# 397881-L.net
KiCad netlist of a schematic drawn in Altium Designer
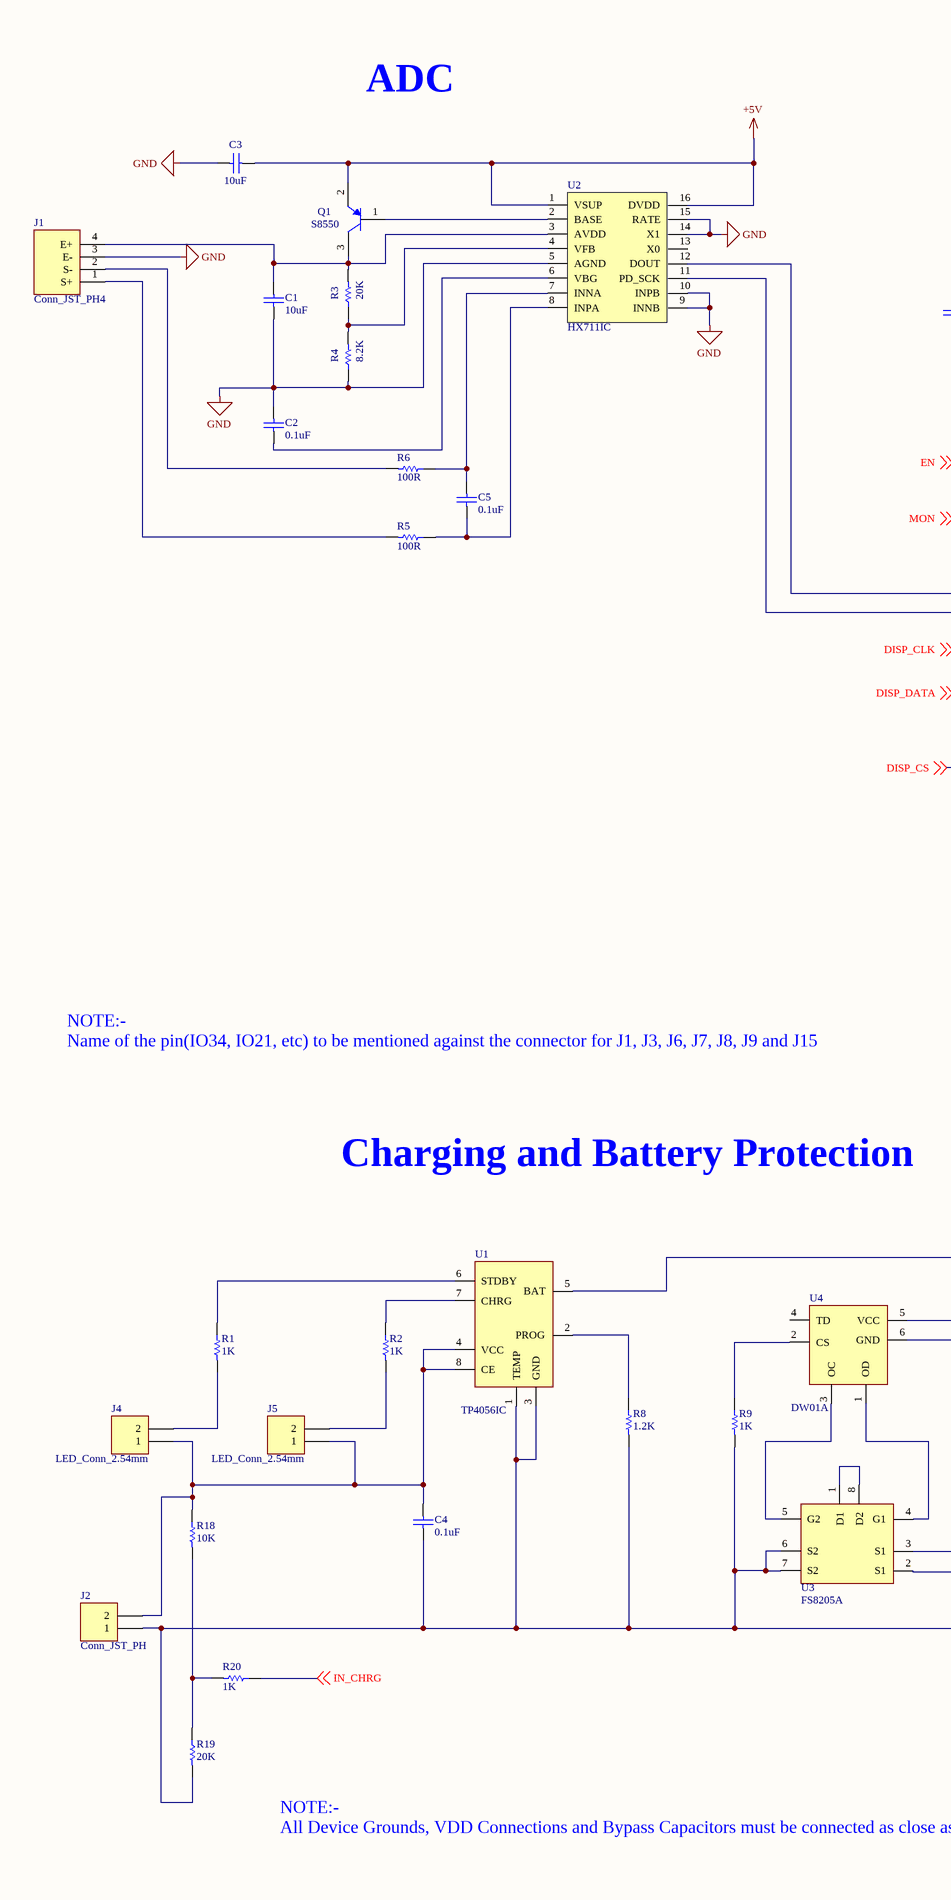
[diagram p0: 397881-L.SchDoc, left]
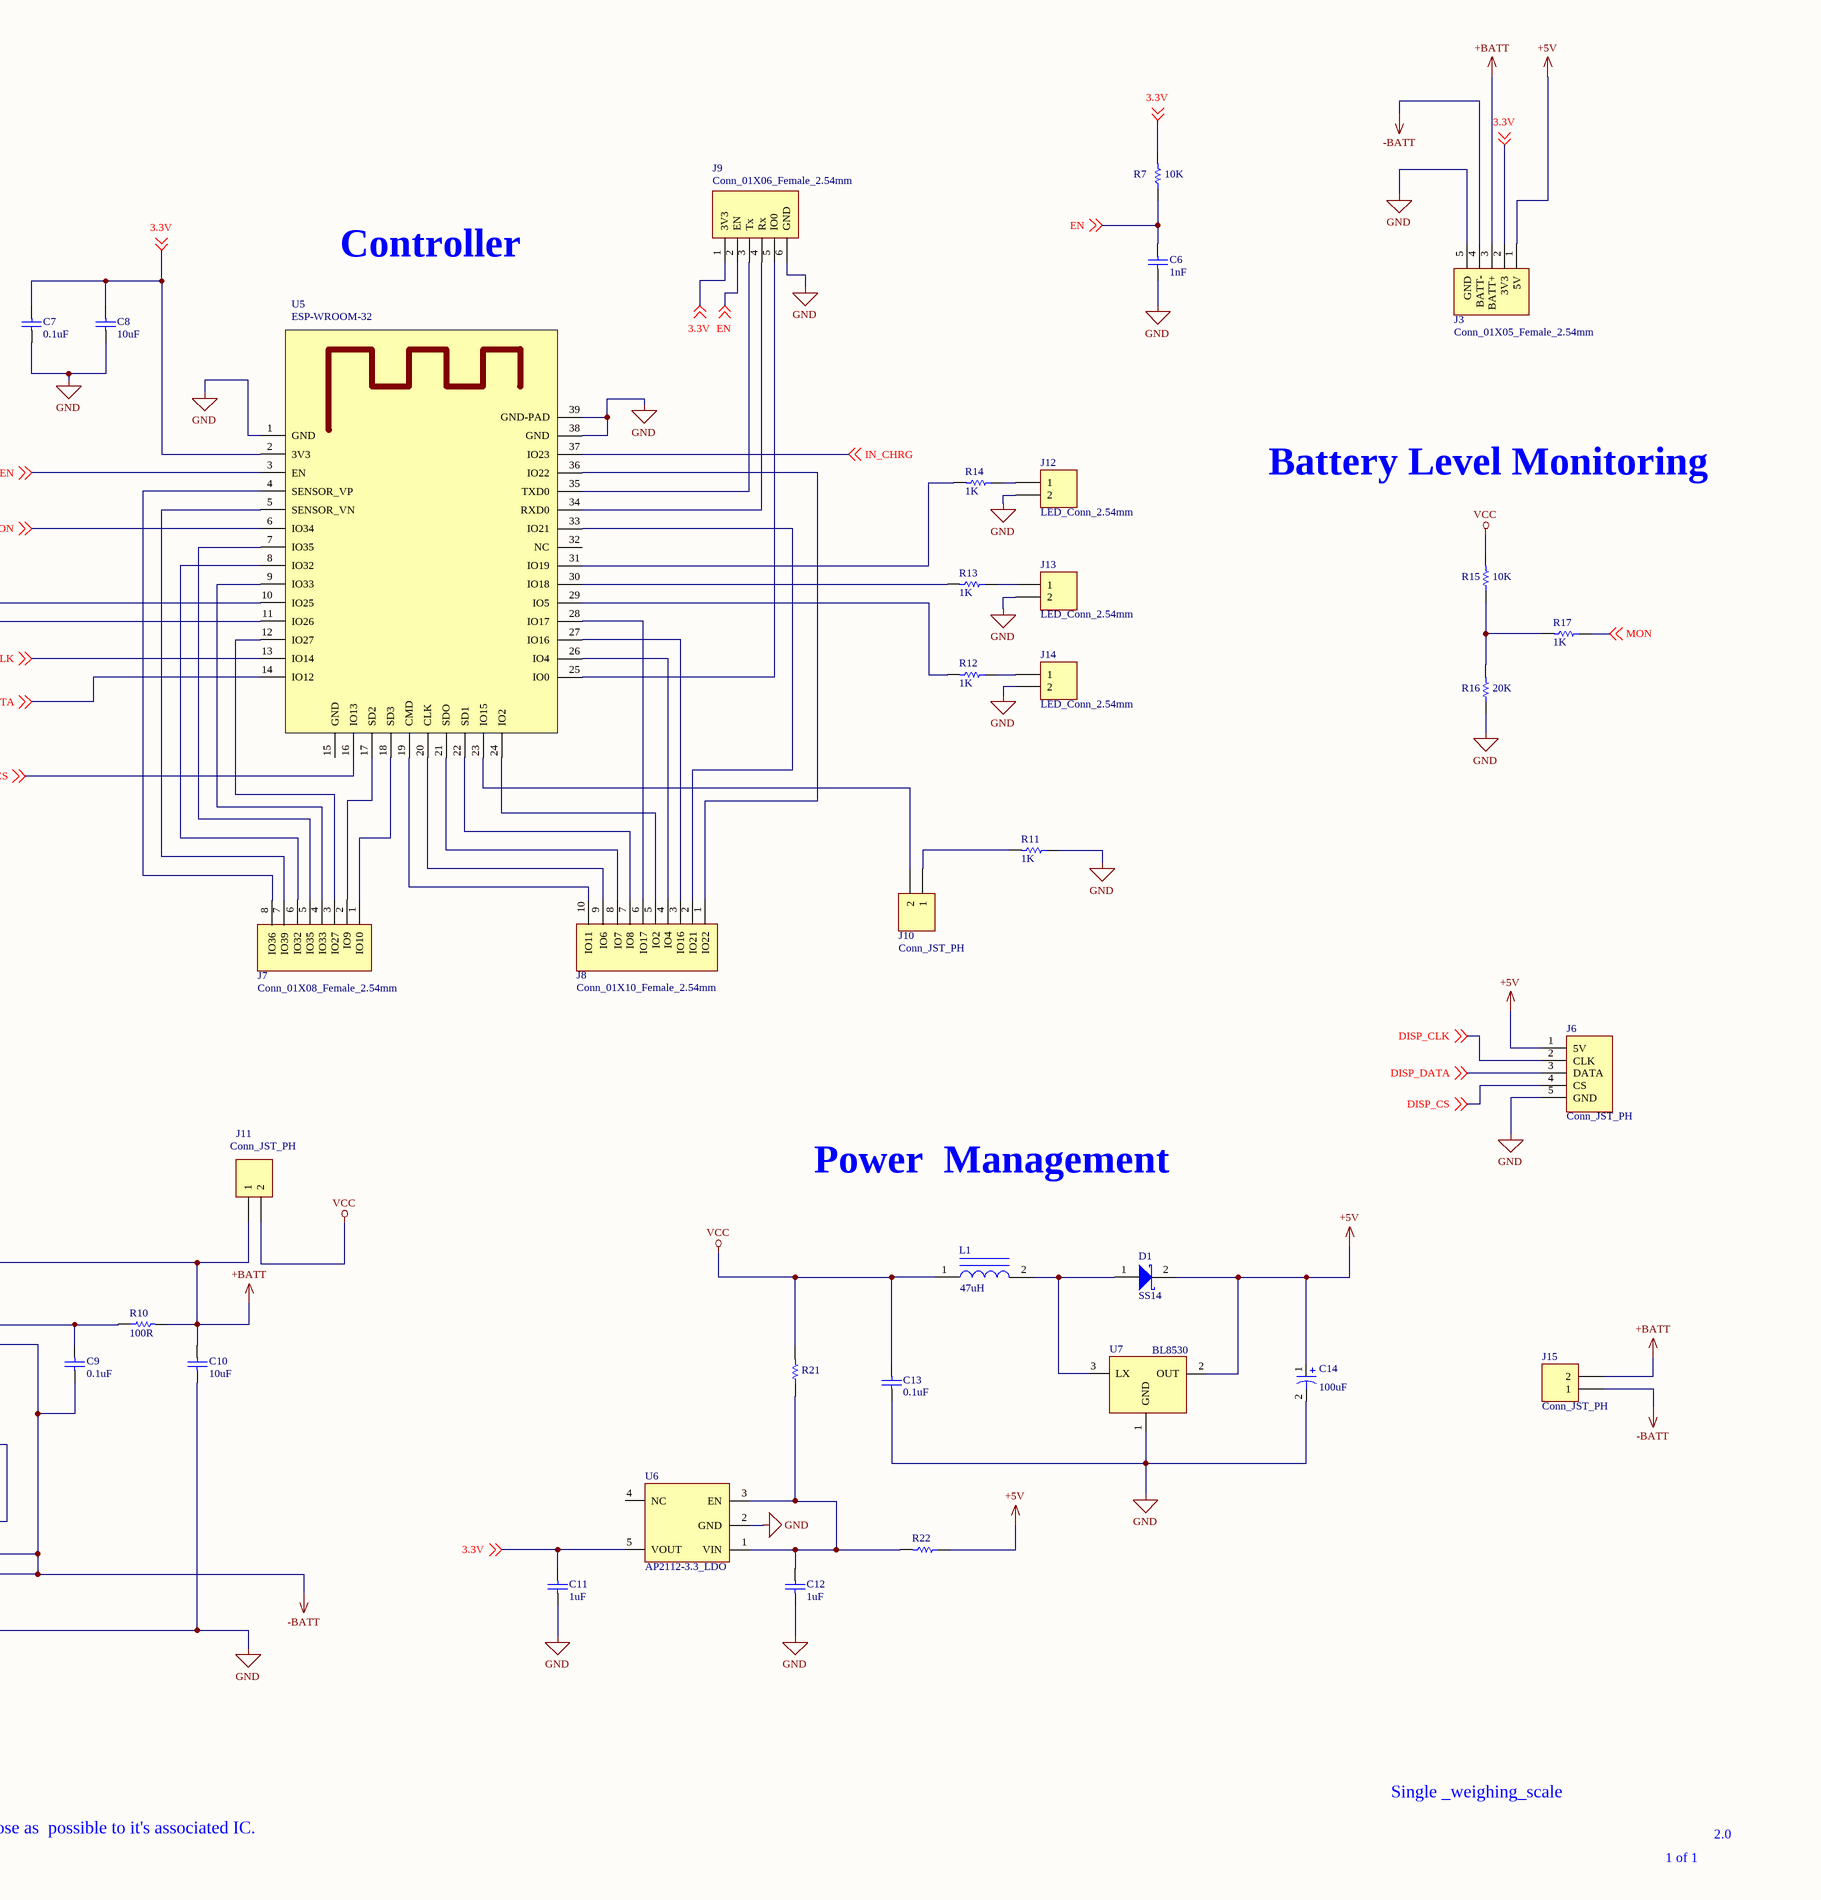
[diagram p1: 397881-L.SchDoc, right]

(export (version "E")
  (design (tool "Eeschema 10.0.6"))
  (components
    (comp (ref "C1")
      (value "10uF")
      (footprint "C0603")
      (description "Capacitor")
      (fields (field (name "Comment") "Cap") (field (name "PUBLISHER") "Altium Limited"))
      (libsource (lib "Miscellaneous Devices") (part "Cap"))
    )
    (comp (ref "C2")
      (value "0.1uF")
      (footprint "C0603")
      (description "Capacitor")
      (fields (field (name "Comment") "Cap") (field (name "PUBLISHER") "Altium Limited"))
      (libsource (lib "Miscellaneous Devices") (part "Cap"))
    )
    (comp (ref "C3")
      (value "10uF")
      (footprint "C0603")
      (description "Capacitor")
      (fields (field (name "Comment") "Cap") (field (name "PUBLISHER") "Altium Limited"))
      (libsource (lib "Miscellaneous Devices") (part "Cap"))
    )
    (comp (ref "C4")
      (value "0.1uF")
      (footprint "C0603")
      (description "Capacitor")
      (fields (field (name "Comment") "Cap") (field (name "PUBLISHER") "Altium Limited"))
      (libsource (lib "Miscellaneous Devices") (part "Cap"))
    )
    (comp (ref "C5")
      (value "0.1uF")
      (footprint "C0603")
      (description "Capacitor")
      (fields (field (name "Comment") "Cap") (field (name "PUBLISHER") "Altium Limited"))
      (libsource (lib "Miscellaneous Devices") (part "Cap"))
    )
    (comp (ref "C6")
      (value "1nF")
      (footprint "C0603")
      (description "Capacitor")
      (fields (field (name "Comment") "Cap") (field (name "PUBLISHER") "Altium Limited"))
      (libsource (lib "Miscellaneous Devices") (part "Cap"))
    )
    (comp (ref "C7")
      (value "0.1uF")
      (footprint "C0603")
      (description "Capacitor")
      (fields (field (name "Comment") "Cap") (field (name "PUBLISHER") "Altium Limited"))
      (libsource (lib "Miscellaneous Devices") (part "Cap"))
    )
    (comp (ref "C8")
      (value "10uF")
      (footprint "C0603")
      (description "Capacitor")
      (fields (field (name "Comment") "Cap") (field (name "PUBLISHER") "Altium Limited"))
      (libsource (lib "Miscellaneous Devices") (part "Cap"))
    )
    (comp (ref "C9")
      (value "0.1uF")
      (footprint "C0603")
      (description "Capacitor")
      (fields (field (name "Comment") "Cap") (field (name "PUBLISHER") "Altium Limited"))
      (libsource (lib "Miscellaneous Devices") (part "Cap"))
    )
    (comp (ref "C10")
      (value "10uF")
      (footprint "C0603")
      (description "Capacitor")
      (fields (field (name "Comment") "Cap") (field (name "PUBLISHER") "Altium Limited"))
      (libsource (lib "Miscellaneous Devices") (part "Cap"))
    )
    (comp (ref "C11")
      (value "1uF")
      (footprint "C0603")
      (description "Capacitor")
      (fields (field (name "Comment") "Cap") (field (name "PUBLISHER") "Altium Limited"))
      (libsource (lib "Miscellaneous Devices") (part "Cap"))
    )
    (comp (ref "C12")
      (value "1uF")
      (footprint "C0603")
      (description "Capacitor")
      (fields (field (name "Comment") "Cap") (field (name "PUBLISHER") "Altium Limited"))
      (libsource (lib "Miscellaneous Devices") (part "Cap"))
    )
    (comp (ref "C13")
      (value "0.1uF")
      (footprint "C0603")
      (description "Capacitor")
      (fields (field (name "Comment") "Cap") (field (name "PUBLISHER") "Altium Limited"))
      (libsource (lib "Miscellaneous Devices") (part "Cap"))
    )
    (comp (ref "C14")
      (value "100uF")
      (footprint "C14")
      (description "Polarized Capacitor (Radial)")
      (fields (field (name "Comment") "Cap Pol1") (field (name "PUBLISHER") "Altium Limited"))
      (libsource (lib "Miscellaneous Devices") (part "Cap Pol1"))
    )
    (comp (ref "D1")
      (value "SS14")
      (footprint "D1")
      (description "Schottky Diode")
      (fields (field (name "PUBLISHER") "Altium Limited"))
      (libsource (lib "Miscellaneous Devices") (part "D Schottky"))
    )
    (comp (ref "J1")
      (value "Conn_JST_PH4")
      (footprint "J1")
      (description "Header, 5-Pin")
      (fields (field (name "PUBLISHER") "Altium Limited"))
      (libsource (lib "397881-L") (part "Conn_JST_PH4"))
    )
    (comp (ref "J2")
      (value "Conn_JST_PH")
      (footprint "J2,J10,J11,J15")
      (description "Header, 2-Pin")
      (fields (field (name "PUBLISHER") "Altium Limited"))
      (libsource (lib "") (part "Header 2_1"))
    )
    (comp (ref "J3")
      (value "Conn_01X05_Female_2.54mm")
      (footprint "J3")
      (description "Header, 6-Pin")
      (fields (field (name "PUBLISHER") "Altium Limited"))
      (libsource (lib "397881-L") (part "Conn_01X05_Female_2.54mm"))
    )
    (comp (ref "J4")
      (value "LED_Conn_2.54mm")
      (footprint "J4,J5,J12,J13,J14")
      (description "Header, 2-Pin")
      (fields (field (name "PUBLISHER") "Altium Limited"))
      (libsource (lib "") (part "Header 2_1"))
    )
    (comp (ref "J5")
      (value "LED_Conn_2.54mm")
      (footprint "J4,J5,J12,J13,J14")
      (description "Header, 2-Pin")
      (fields (field (name "PUBLISHER") "Altium Limited"))
      (libsource (lib "") (part "Header 2_1"))
    )
    (comp (ref "J6")
      (value "Conn_JST_PH")
      (footprint "J6")
      (description "Header, 5-Pin")
      (fields (field (name "PUBLISHER") "Altium Limited"))
      (libsource (lib "397881-L") (part "Conn_JST_PH"))
    )
    (comp (ref "J7")
      (value "Conn_01X08_Female_2.54mm")
      (footprint "J7")
      (description "Header, 6-Pin")
      (fields (field (name "PUBLISHER") "Altium Limited"))
      (libsource (lib "397881-L") (part "Conn_01X08_Female_2.54mm"))
    )
    (comp (ref "J8")
      (value "Conn_01X10_Female_2.54mm")
      (footprint "J8")
      (description "Header, 6-Pin")
      (fields (field (name "PUBLISHER") "Altium Limited"))
      (libsource (lib "397881-L") (part "Conn_01X10_Female_2.54mm"))
    )
    (comp (ref "J9")
      (value "Conn_01X06_Female_2.54mm")
      (footprint "J9")
      (description "Header, 6-Pin")
      (fields (field (name "PUBLISHER") "Altium Limited"))
      (libsource (lib "397881-L") (part "Conn_01X06_Female_2.54mm"))
    )
    (comp (ref "J10")
      (value "Conn_JST_PH")
      (footprint "J2,J10,J11,J15")
      (description "Header, 2-Pin")
      (fields (field (name "PUBLISHER") "Altium Limited"))
      (libsource (lib "") (part "Header 2_2"))
    )
    (comp (ref "J11")
      (value "Conn_JST_PH")
      (footprint "J2,J10,J11,J15")
      (description "Header, 2-Pin")
      (fields (field (name "PUBLISHER") "Altium Limited"))
      (libsource (lib "") (part "Header 2_3"))
    )
    (comp (ref "J12")
      (value "LED_Conn_2.54mm")
      (footprint "J4,J5,J12,J13,J14")
      (description "Header, 2-Pin")
      (fields (field (name "PUBLISHER") "Altium Limited"))
      (libsource (lib "Miscellaneous Connectors") (part "Header 2"))
    )
    (comp (ref "J13")
      (value "LED_Conn_2.54mm")
      (footprint "J4,J5,J12,J13,J14")
      (description "Header, 2-Pin")
      (fields (field (name "PUBLISHER") "Altium Limited"))
      (libsource (lib "Miscellaneous Connectors") (part "Header 2"))
    )
    (comp (ref "J14")
      (value "LED_Conn_2.54mm")
      (footprint "J4,J5,J12,J13,J14")
      (description "Header, 2-Pin")
      (fields (field (name "PUBLISHER") "Altium Limited"))
      (libsource (lib "Miscellaneous Connectors") (part "Header 2"))
    )
    (comp (ref "J15")
      (value "Conn_JST_PH")
      (footprint "J2,J10,J11,J15")
      (description "Header, 2-Pin")
      (fields (field (name "PUBLISHER") "Altium Limited"))
      (libsource (lib "") (part "Header 2_1"))
    )
    (comp (ref "L1")
      (value "47uH")
      (footprint "L1")
      (description "Magnetic-Core Inductor")
      (fields (field (name "Comment") "Inductor Iron") (field (name "PUBLISHER") "Altium Limited"))
      (libsource (lib "Miscellaneous Devices") (part "Inductor Iron"))
    )
    (comp (ref "Q1")
      (value "S8550")
      (footprint "Q1")
      (description "PNP Bipolar Transistor")
      (fields (field (name "PUBLISHER") "Altium Limited"))
      (libsource (lib "Miscellaneous Devices") (part "PNP"))
    )
    (comp (ref "R1")
      (value "1K")
      (footprint "R0603")
      (description "Resistor")
      (fields (field (name "Comment") "Res1") (field (name "PUBLISHER") "Altium Limited"))
      (libsource (lib "Miscellaneous Devices") (part "Res1"))
    )
    (comp (ref "R2")
      (value "1K")
      (footprint "R0603")
      (description "Resistor")
      (fields (field (name "Comment") "Res1") (field (name "PUBLISHER") "Altium Limited"))
      (libsource (lib "Miscellaneous Devices") (part "Res1"))
    )
    (comp (ref "R3")
      (value "20K")
      (footprint "R0603")
      (description "Resistor")
      (fields (field (name "Comment") "Res1") (field (name "PUBLISHER") "Altium Limited"))
      (libsource (lib "Miscellaneous Devices") (part "Res1"))
    )
    (comp (ref "R4")
      (value "8.2K")
      (footprint "R0603")
      (description "Resistor")
      (fields (field (name "Comment") "Res1") (field (name "PUBLISHER") "Altium Limited"))
      (libsource (lib "Miscellaneous Devices") (part "Res1"))
    )
    (comp (ref "R5")
      (value "100R")
      (footprint "R0603")
      (description "Resistor")
      (fields (field (name "Comment") "Res1") (field (name "PUBLISHER") "Altium Limited"))
      (libsource (lib "Miscellaneous Devices") (part "Res1"))
    )
    (comp (ref "R6")
      (value "100R")
      (footprint "R0603")
      (description "Resistor")
      (fields (field (name "Comment") "Res1") (field (name "PUBLISHER") "Altium Limited"))
      (libsource (lib "Miscellaneous Devices") (part "Res1"))
    )
    (comp (ref "R7")
      (value "10K")
      (footprint "R0603")
      (description "Resistor")
      (fields (field (name "Comment") "Res1") (field (name "PUBLISHER") "Altium Limited"))
      (libsource (lib "Miscellaneous Devices") (part "Res1"))
    )
    (comp (ref "R8")
      (value "1.2K")
      (footprint "R0603")
      (description "Resistor")
      (fields (field (name "Comment") "Res1") (field (name "PUBLISHER") "Altium Limited"))
      (libsource (lib "Miscellaneous Devices") (part "Res1"))
    )
    (comp (ref "R9")
      (value "1K")
      (footprint "R0603")
      (description "Resistor")
      (fields (field (name "Comment") "Res1") (field (name "PUBLISHER") "Altium Limited"))
      (libsource (lib "Miscellaneous Devices") (part "Res1"))
    )
    (comp (ref "R10")
      (value "100R")
      (footprint "R0603")
      (description "Resistor")
      (fields (field (name "Comment") "Res1") (field (name "PUBLISHER") "Altium Limited"))
      (libsource (lib "Miscellaneous Devices") (part "Res1"))
    )
    (comp (ref "R11")
      (value "1K")
      (footprint "R0603")
      (description "Resistor")
      (fields (field (name "Comment") "Res1") (field (name "PUBLISHER") "Altium Limited"))
      (libsource (lib "Miscellaneous Devices") (part "Res1"))
    )
    (comp (ref "R12")
      (value "1K")
      (footprint "R0603")
      (description "Resistor")
      (fields (field (name "Comment") "Res1") (field (name "PUBLISHER") "Altium Limited"))
      (libsource (lib "Miscellaneous Devices") (part "Res1"))
    )
    (comp (ref "R13")
      (value "1K")
      (footprint "R0603")
      (description "Resistor")
      (fields (field (name "Comment") "Res1") (field (name "PUBLISHER") "Altium Limited"))
      (libsource (lib "Miscellaneous Devices") (part "Res1"))
    )
    (comp (ref "R14")
      (value "1K")
      (footprint "R0603")
      (description "Resistor")
      (fields (field (name "Comment") "Res1") (field (name "PUBLISHER") "Altium Limited"))
      (libsource (lib "Miscellaneous Devices") (part "Res1"))
    )
    (comp (ref "R15")
      (value "10K")
      (footprint "R0603")
      (description "Resistor")
      (fields (field (name "Comment") "Res1") (field (name "PUBLISHER") "Altium Limited"))
      (libsource (lib "Miscellaneous Devices") (part "Res1"))
    )
    (comp (ref "R16")
      (value "20K")
      (footprint "R0603")
      (description "Resistor")
      (fields (field (name "Comment") "Res1") (field (name "PUBLISHER") "Altium Limited"))
      (libsource (lib "Miscellaneous Devices") (part "Res1"))
    )
    (comp (ref "R17")
      (value "1K")
      (footprint "R0603")
      (description "Resistor")
      (fields (field (name "Comment") "Res1") (field (name "PUBLISHER") "Altium Limited"))
      (libsource (lib "Miscellaneous Devices") (part "Res1"))
    )
    (comp (ref "R18")
      (value "10K")
      (footprint "R0603")
      (description "Resistor")
      (fields (field (name "Comment") "Res1") (field (name "PUBLISHER") "Altium Limited"))
      (libsource (lib "Miscellaneous Devices") (part "Res1"))
    )
    (comp (ref "R19")
      (value "20K")
      (footprint "R0603")
      (description "Resistor")
      (fields (field (name "Comment") "Res1") (field (name "PUBLISHER") "Altium Limited"))
      (libsource (lib "Miscellaneous Devices") (part "Res1"))
    )
    (comp (ref "R20")
      (value "1K")
      (footprint "R0603")
      (description "Resistor")
      (fields (field (name "Comment") "Res1") (field (name "PUBLISHER") "Altium Limited"))
      (libsource (lib "Miscellaneous Devices") (part "Res1"))
    )
    (comp (ref "R21")
      (value "Res1")
      (footprint "R0603")
      (description "Resistor")
      (fields (field (name "PUBLISHER") "Altium Limited"))
      (libsource (lib "Miscellaneous Devices") (part "Res1"))
    )
    (comp (ref "R22")
      (value "Res1")
      (footprint "R0603")
      (description "Resistor")
      (fields (field (name "PUBLISHER") "Altium Limited"))
      (libsource (lib "Miscellaneous Devices") (part "Res1"))
    )
    (comp (ref "U1") (value "TP4056IC") (footprint "U1") (libsource (lib "397881-L") (part "TP4056IC")))
    (comp (ref "U2") (value "HX711IC") (libsource (lib "397881-L") (part "HX711IC")))
    (comp (ref "U3") (value "FS8205A") (footprint "U3") (libsource (lib "397881-L") (part "FS8205A")))
    (comp (ref "U4") (value "DW01A") (footprint "U4") (libsource (lib "397881-L") (part "DW01A")))
    (comp (ref "U5")
      (value "ESP-WROOM-32")
      (footprint "U5")
      (libsource (lib "397881-L") (part "ESP-WROOM-32"))
    )
    (comp (ref "U6")
      (value "AP2112-3.3_LDO")
      (footprint "U6")
      (libsource (lib "397881-L") (part "AP2112-3.3_LDO"))
    )
    (comp (ref "U7") (value "BL8530") (footprint "U7") (libsource (lib "397881-L") (part "BL8530")))
  )
  (nets
    (net (code "1") (name "+5V") (class "Default")
      (node (ref "C14") (pin "1") (pinfunction "1_1") (pintype "passive"))
      (node (ref "C3") (pin "2") (pinfunction "2_2") (pintype "passive"))
      (node (ref "D1") (pin "2") (pinfunction "K_2") (pintype "passive"))
      (node (ref "J3") (pin "1") (pinfunction "5V_1") (pintype "passive"))
      (node (ref "J6") (pin "1") (pinfunction "5V_1") (pintype "passive"))
      (node (ref "Q1") (pin "2") (pinfunction "E_2") (pintype "passive"))
      (node (ref "R22") (pin "1") (pinfunction "1_1") (pintype "passive"))
      (node (ref "U2") (pin "1") (pinfunction "VSUP_1") (pintype "passive"))
      (node (ref "U2") (pin "16") (pinfunction "DVDD_16") (pintype "passive"))
      (node (ref "U7") (pin "2") (pinfunction "OUT_2") (pintype "passive"))
    )
    (net (code "2") (name "+BATT") (class "Default")
      (node (ref "C10") (pin "2") (pinfunction "2_2") (pintype "passive"))
      (node (ref "J11") (pin "1") (pinfunction "1_1") (pintype "passive"))
      (node (ref "J15") (pin "2") (pinfunction "2_2") (pintype "passive"))
      (node (ref "J3") (pin "3") (pinfunction "BATT+_3") (pintype "passive"))
      (node (ref "R10") (pin "2") (pinfunction "2_2") (pintype "passive"))
      (node (ref "U1") (pin "5") (pinfunction "BAT_5") (pintype "passive"))
    )
    (net (code "3") (name "-BATT") (class "Default")
      (node (ref "C9") (pin "1") (pinfunction "1_1") (pintype "passive"))
      (node (ref "J15") (pin "1") (pinfunction "1_1") (pintype "passive"))
      (node (ref "J3") (pin "4") (pinfunction "BATT-_4") (pintype "passive"))
      (node (ref "U3") (pin "2") (pinfunction "S1_2") (pintype "passive"))
      (node (ref "U3") (pin "3") (pinfunction "S1_3") (pintype "passive"))
      (node (ref "U4") (pin "6") (pinfunction "GND_6") (pintype "passive"))
    )
    (net (code "4") (name "3.3V") (class "Default")
      (node (ref "C11") (pin "2") (pinfunction "2_2") (pintype "passive"))
      (node (ref "C7") (pin "2") (pinfunction "2_2") (pintype "passive"))
      (node (ref "C8") (pin "2") (pinfunction "2_2") (pintype "passive"))
      (node (ref "J3") (pin "2") (pinfunction "3V3_2") (pintype "passive"))
      (node (ref "J9") (pin "1") (pinfunction "3V3_1") (pintype "passive"))
      (node (ref "R7") (pin "2") (pinfunction "2_2") (pintype "passive"))
      (node (ref "U5") (pin "2") (pinfunction "3V3_2") (pintype "passive"))
      (node (ref "U6") (pin "5") (pinfunction "VOUT_5") (pintype "passive"))
    )
    (net (code "5") (name "DISP_CLK") (class "Default")
      (node (ref "J6") (pin "2") (pinfunction "CLK_2") (pintype "passive"))
      (node (ref "U5") (pin "13") (pinfunction "IO14_13") (pintype "passive"))
    )
    (net (code "6") (name "DISP_CS") (class "Default")
      (node (ref "J6") (pin "4") (pinfunction "CS_4") (pintype "passive"))
      (node (ref "U5") (pin "16") (pinfunction "IO13_16") (pintype "passive"))
    )
    (net (code "7") (name "DISP_DATA") (class "Default")
      (node (ref "J6") (pin "3") (pinfunction "DATA_3") (pintype "passive"))
      (node (ref "U5") (pin "14") (pinfunction "IO12_14") (pintype "passive"))
    )
    (net (code "8") (name "EN") (class "Default")
      (node (ref "C6") (pin "2") (pinfunction "2_2") (pintype "passive"))
      (node (ref "J9") (pin "2") (pinfunction "EN_2") (pintype "passive"))
      (node (ref "R7") (pin "1") (pinfunction "1_1") (pintype "passive"))
      (node (ref "U5") (pin "3") (pinfunction "EN_3") (pintype "passive"))
    )
    (net (code "9") (name "GND") (class "Default")
      (node (ref "C1") (pin "1") (pinfunction "1_1") (pintype "passive"))
      (node (ref "C10") (pin "1") (pinfunction "1_1") (pintype "passive"))
      (node (ref "C11") (pin "1") (pinfunction "1_1") (pintype "passive"))
      (node (ref "C12") (pin "1") (pinfunction "1_1") (pintype "passive"))
      (node (ref "C13") (pin "1") (pinfunction "1_1") (pintype "passive"))
      (node (ref "C14") (pin "2") (pinfunction "2_2") (pintype "passive"))
      (node (ref "C2") (pin "2") (pinfunction "2_2") (pintype "passive"))
      (node (ref "C3") (pin "1") (pinfunction "1_1") (pintype "passive"))
      (node (ref "C4") (pin "1") (pinfunction "1_1") (pintype "passive"))
      (node (ref "C6") (pin "1") (pinfunction "1_1") (pintype "passive"))
      (node (ref "C7") (pin "1") (pinfunction "1_1") (pintype "passive"))
      (node (ref "C8") (pin "1") (pinfunction "1_1") (pintype "passive"))
      (node (ref "J1") (pin "3") (pinfunction "E-_3") (pintype "passive"))
      (node (ref "J12") (pin "2") (pinfunction "2_2") (pintype "passive"))
      (node (ref "J13") (pin "2") (pinfunction "2_2") (pintype "passive"))
      (node (ref "J14") (pin "2") (pinfunction "2_2") (pintype "passive"))
      (node (ref "J2") (pin "1") (pinfunction "1_1") (pintype "passive"))
      (node (ref "J3") (pin "5") (pinfunction "GND_5") (pintype "passive"))
      (node (ref "J6") (pin "5") (pinfunction "GND_5") (pintype "passive"))
      (node (ref "J9") (pin "6") (pinfunction "GND_6") (pintype "passive"))
      (node (ref "R11") (pin "1") (pinfunction "1_1") (pintype "passive"))
      (node (ref "R16") (pin "1") (pinfunction "1_1") (pintype "passive"))
      (node (ref "R19") (pin "2") (pinfunction "2_2") (pintype "passive"))
      (node (ref "R4") (pin "1") (pinfunction "1_1") (pintype "passive"))
      (node (ref "R8") (pin "2") (pinfunction "2_2") (pintype "passive"))
      (node (ref "R9") (pin "2") (pinfunction "2_2") (pintype "passive"))
      (node (ref "U1") (pin "1") (pinfunction "TEMP_1") (pintype "passive"))
      (node (ref "U1") (pin "3") (pinfunction "GND_3") (pintype "passive"))
      (node (ref "U2") (pin "10") (pinfunction "INPB_10") (pintype "passive"))
      (node (ref "U2") (pin "14") (pinfunction "X1_14") (pintype "passive"))
      (node (ref "U2") (pin "15") (pinfunction "RATE_15") (pintype "passive"))
      (node (ref "U2") (pin "5") (pinfunction "AGND_5") (pintype "passive"))
      (node (ref "U2") (pin "9") (pinfunction "INNB_9") (pintype "passive"))
      (node (ref "U3") (pin "6") (pinfunction "S2_6") (pintype "passive"))
      (node (ref "U3") (pin "7") (pinfunction "S2_7") (pintype "passive"))
      (node (ref "U5") (pin "1") (pinfunction "GND_1") (pintype "passive"))
      (node (ref "U5") (pin "38") (pinfunction "GND_38") (pintype "passive"))
      (node (ref "U5") (pin "39") (pinfunction "GND-PAD_39") (pintype "passive"))
      (node (ref "U6") (pin "2") (pinfunction "GND_2") (pintype "passive"))
      (node (ref "U7") (pin "1") (pinfunction "GND_1") (pintype "passive"))
    )
    (net (code "10") (name "IN_CHRG") (class "Default")
      (node (ref "R20") (pin "1") (pinfunction "1_1") (pintype "passive"))
      (node (ref "U5") (pin "37") (pinfunction "IO23_37") (pintype "passive"))
    )
    (net (code "11") (name "MON") (class "Default")
      (node (ref "R17") (pin "1") (pinfunction "1_1") (pintype "passive"))
      (node (ref "U5") (pin "6") (pinfunction "IO34_6") (pintype "passive"))
    )
    (net (code "12") (name "Net-(D1-A)") (class "Default")
      (node (ref "D1") (pin "1") (pinfunction "A_1") (pintype "passive"))
      (node (ref "L1") (pin "2") (pinfunction "2_2") (pintype "passive"))
      (node (ref "U7") (pin "3") (pinfunction "LX_3") (pintype "passive"))
    )
    (net (code "13") (name "Net-(J1-E+)") (class "Default")
      (node (ref "C1") (pin "2") (pinfunction "2_2") (pintype "passive"))
      (node (ref "J1") (pin "4") (pinfunction "E+_4") (pintype "passive"))
      (node (ref "Q1") (pin "3") (pinfunction "C_3") (pintype "passive"))
      (node (ref "R3") (pin "2") (pinfunction "2_2") (pintype "passive"))
      (node (ref "U2") (pin "3") (pinfunction "AVDD_3") (pintype "passive"))
    )
    (net (code "14") (name "Net-(J1-S+)") (class "Default")
      (node (ref "J1") (pin "1") (pinfunction "S+_1") (pintype "passive"))
      (node (ref "R5") (pin "2") (pinfunction "2_2") (pintype "passive"))
    )
    (net (code "15") (name "Net-(J1-S-)") (class "Default")
      (node (ref "J1") (pin "2") (pinfunction "S-_2") (pintype "passive"))
      (node (ref "R6") (pin "2") (pinfunction "2_2") (pintype "passive"))
    )
    (net (code "16") (name "Net-(J4-Pad2)") (class "Default")
      (node (ref "J4") (pin "2") (pinfunction "2_2") (pintype "passive"))
      (node (ref "R1") (pin "2") (pinfunction "2_2") (pintype "passive"))
    )
    (net (code "17") (name "Net-(J5-Pad2)") (class "Default")
      (node (ref "J5") (pin "2") (pinfunction "2_2") (pintype "passive"))
      (node (ref "R2") (pin "2") (pinfunction "2_2") (pintype "passive"))
    )
    (net (code "18") (name "Net-(J7-IO9)") (class "Default")
      (node (ref "J7") (pin "2") (pinfunction "IO9_2") (pintype "passive"))
      (node (ref "U5") (pin "17") (pinfunction "SD2_17") (pintype "passive"))
    )
    (net (code "19") (name "Net-(J7-IO10)") (class "Default")
      (node (ref "J7") (pin "1") (pinfunction "IO10_1") (pintype "passive"))
      (node (ref "U5") (pin "18") (pinfunction "SD3_18") (pintype "passive"))
    )
    (net (code "20") (name "Net-(J7-IO27)") (class "Default")
      (node (ref "J7") (pin "3") (pinfunction "IO27_3") (pintype "passive"))
      (node (ref "U5") (pin "12") (pinfunction "IO27_12") (pintype "passive"))
    )
    (net (code "21") (name "Net-(J7-IO32)") (class "Default")
      (node (ref "J7") (pin "6") (pinfunction "IO32_6") (pintype "passive"))
      (node (ref "U5") (pin "8") (pinfunction "IO32_8") (pintype "passive"))
    )
    (net (code "22") (name "Net-(J7-IO33)") (class "Default")
      (node (ref "J7") (pin "4") (pinfunction "IO33_4") (pintype "passive"))
      (node (ref "U5") (pin "9") (pinfunction "IO33_9") (pintype "passive"))
    )
    (net (code "23") (name "Net-(J7-IO35)") (class "Default")
      (node (ref "J7") (pin "5") (pinfunction "IO35_5") (pintype "passive"))
      (node (ref "U5") (pin "7") (pinfunction "IO35_7") (pintype "passive"))
    )
    (net (code "24") (name "Net-(J7-IO36)") (class "Default")
      (node (ref "J7") (pin "8") (pinfunction "IO36_8") (pintype "passive"))
      (node (ref "U5") (pin "4") (pinfunction "SENSOR_VP_4") (pintype "passive"))
    )
    (net (code "25") (name "Net-(J7-IO39)") (class "Default")
      (node (ref "J7") (pin "7") (pinfunction "IO39_7") (pintype "passive"))
      (node (ref "U5") (pin "5") (pinfunction "SENSOR_VN_5") (pintype "passive"))
    )
    (net (code "26") (name "Net-(J8-IO2)") (class "Default")
      (node (ref "J8") (pin "5") (pinfunction "IO2_5") (pintype "passive"))
      (node (ref "U5") (pin "24") (pinfunction "IO2_24") (pintype "passive"))
    )
    (net (code "27") (name "Net-(J8-IO4)") (class "Default")
      (node (ref "J8") (pin "4") (pinfunction "IO4_4") (pintype "passive"))
      (node (ref "U5") (pin "26") (pinfunction "IO4_26") (pintype "passive"))
    )
    (net (code "28") (name "Net-(J8-IO6)") (class "Default")
      (node (ref "J8") (pin "9") (pinfunction "IO6_9") (pintype "passive"))
      (node (ref "U5") (pin "20") (pinfunction "CLK_20") (pintype "passive"))
    )
    (net (code "29") (name "Net-(J8-IO7)") (class "Default")
      (node (ref "J8") (pin "8") (pinfunction "IO7_8") (pintype "passive"))
      (node (ref "U5") (pin "21") (pinfunction "SDO_21") (pintype "passive"))
    )
    (net (code "30") (name "Net-(J8-IO8)") (class "Default")
      (node (ref "J8") (pin "7") (pinfunction "IO8_7") (pintype "passive"))
      (node (ref "U5") (pin "22") (pinfunction "SD1_22") (pintype "passive"))
    )
    (net (code "31") (name "Net-(J8-IO11)") (class "Default")
      (node (ref "J8") (pin "10") (pinfunction "IO11_10") (pintype "passive"))
      (node (ref "U5") (pin "19") (pinfunction "CMD_19") (pintype "passive"))
    )
    (net (code "32") (name "Net-(J8-IO16)") (class "Default")
      (node (ref "J8") (pin "3") (pinfunction "IO16_3") (pintype "passive"))
      (node (ref "U5") (pin "27") (pinfunction "IO16_27") (pintype "passive"))
    )
    (net (code "33") (name "Net-(J8-IO17)") (class "Default")
      (node (ref "J8") (pin "6") (pinfunction "IO17_6") (pintype "passive"))
      (node (ref "U5") (pin "28") (pinfunction "IO17_28") (pintype "passive"))
    )
    (net (code "34") (name "Net-(J8-IO21)") (class "Default")
      (node (ref "J8") (pin "2") (pinfunction "IO21_2") (pintype "passive"))
      (node (ref "U5") (pin "33") (pinfunction "IO21_33") (pintype "passive"))
    )
    (net (code "35") (name "Net-(J8-IO22)") (class "Default")
      (node (ref "J8") (pin "1") (pinfunction "IO22_1") (pintype "passive"))
      (node (ref "U5") (pin "36") (pinfunction "IO22_36") (pintype "passive"))
    )
    (net (code "36") (name "Net-(J9-IO0)") (class "Default")
      (node (ref "J9") (pin "5") (pinfunction "IO0_5") (pintype "passive"))
      (node (ref "U5") (pin "25") (pinfunction "IO0_25") (pintype "passive"))
    )
    (net (code "37") (name "Net-(J9-Rx)") (class "Default")
      (node (ref "J9") (pin "4") (pinfunction "Rx_4") (pintype "passive"))
      (node (ref "U5") (pin "34") (pinfunction "RXD0_34") (pintype "passive"))
    )
    (net (code "38") (name "Net-(J9-Tx)") (class "Default")
      (node (ref "J9") (pin "3") (pinfunction "Tx_3") (pintype "passive"))
      (node (ref "U5") (pin "35") (pinfunction "TXD0_35") (pintype "passive"))
    )
    (net (code "39") (name "Net-(J10-Pad1)") (class "Default")
      (node (ref "J10") (pin "1") (pinfunction "1_1") (pintype "passive"))
      (node (ref "R11") (pin "2") (pinfunction "2_2") (pintype "passive"))
    )
    (net (code "40") (name "Net-(J12-Pad1)") (class "Default")
      (node (ref "J12") (pin "1") (pinfunction "1_1") (pintype "passive"))
      (node (ref "R14") (pin "1") (pinfunction "1_1") (pintype "passive"))
    )
    (net (code "41") (name "Net-(J13-Pad1)") (class "Default")
      (node (ref "J13") (pin "1") (pinfunction "1_1") (pintype "passive"))
      (node (ref "R13") (pin "1") (pinfunction "1_1") (pintype "passive"))
    )
    (net (code "42") (name "Net-(J14-Pad1)") (class "Default")
      (node (ref "J14") (pin "1") (pinfunction "1_1") (pintype "passive"))
      (node (ref "R12") (pin "1") (pinfunction "1_1") (pintype "passive"))
    )
    (net (code "43") (name "Net-(Q1-B)") (class "Default")
      (node (ref "Q1") (pin "1") (pinfunction "B_1") (pintype "passive"))
      (node (ref "U2") (pin "2") (pinfunction "BASE_2") (pintype "passive"))
    )
    (net (code "44") (name "Net-(R15-Pad1)") (class "Default")
      (node (ref "R15") (pin "1") (pinfunction "1_1") (pintype "passive"))
      (node (ref "R16") (pin "2") (pinfunction "2_2") (pintype "passive"))
      (node (ref "R17") (pin "2") (pinfunction "2_2") (pintype "passive"))
    )
    (net (code "45") (name "Net-(R18-Pad2)") (class "Default")
      (node (ref "R18") (pin "2") (pinfunction "2_2") (pintype "passive"))
      (node (ref "R19") (pin "1") (pinfunction "1_1") (pintype "passive"))
      (node (ref "R20") (pin "2") (pinfunction "2_2") (pintype "passive"))
    )
    (net (code "46") (name "Net-(U1-CE)") (class "Default")
      (node (ref "C4") (pin "2") (pinfunction "2_2") (pintype "passive"))
      (node (ref "J2") (pin "2") (pinfunction "2_2") (pintype "passive"))
      (node (ref "J4") (pin "1") (pinfunction "1_1") (pintype "passive"))
      (node (ref "J5") (pin "1") (pinfunction "1_1") (pintype "passive"))
      (node (ref "R18") (pin "1") (pinfunction "1_1") (pintype "passive"))
      (node (ref "U1") (pin "4") (pinfunction "VCC_4") (pintype "passive"))
      (node (ref "U1") (pin "8") (pinfunction "CE_8") (pintype "passive"))
    )
    (net (code "47") (name "Net-(U1-CHRG)") (class "Default")
      (node (ref "R2") (pin "1") (pinfunction "1_1") (pintype "passive"))
      (node (ref "U1") (pin "7") (pinfunction "CHRG_7") (pintype "passive"))
    )
    (net (code "48") (name "Net-(U1-PROG)") (class "Default")
      (node (ref "R8") (pin "1") (pinfunction "1_1") (pintype "passive"))
      (node (ref "U1") (pin "2") (pinfunction "PROG_2") (pintype "passive"))
    )
    (net (code "49") (name "Net-(U1-STDBY)") (class "Default")
      (node (ref "R1") (pin "1") (pinfunction "1_1") (pintype "passive"))
      (node (ref "U1") (pin "6") (pinfunction "STDBY_6") (pintype "passive"))
    )
    (net (code "50") (name "Net-(U2-DOUT)") (class "Default")
      (node (ref "U2") (pin "12") (pinfunction "DOUT_12") (pintype "passive"))
      (node (ref "U5") (pin "10") (pinfunction "IO25_10") (pintype "passive"))
    )
    (net (code "51") (name "Net-(U2-INNA)") (class "Default")
      (node (ref "C5") (pin "2") (pinfunction "2_2") (pintype "passive"))
      (node (ref "R6") (pin "1") (pinfunction "1_1") (pintype "passive"))
      (node (ref "U2") (pin "7") (pinfunction "INNA_7") (pintype "passive"))
    )
    (net (code "52") (name "Net-(U2-INPA)") (class "Default")
      (node (ref "C5") (pin "1") (pinfunction "1_1") (pintype "passive"))
      (node (ref "R5") (pin "1") (pinfunction "1_1") (pintype "passive"))
      (node (ref "U2") (pin "8") (pinfunction "INPA_8") (pintype "passive"))
    )
    (net (code "53") (name "Net-(U2-PD_SCK)") (class "Default")
      (node (ref "U2") (pin "11") (pinfunction "PD_SCK_11") (pintype "passive"))
      (node (ref "U5") (pin "11") (pinfunction "IO26_11") (pintype "passive"))
    )
    (net (code "54") (name "Net-(U2-VBG)") (class "Default")
      (node (ref "C2") (pin "1") (pinfunction "1_1") (pintype "passive"))
      (node (ref "U2") (pin "6") (pinfunction "VBG_6") (pintype "passive"))
    )
    (net (code "55") (name "Net-(U2-VFB)") (class "Default")
      (node (ref "R3") (pin "1") (pinfunction "1_1") (pintype "passive"))
      (node (ref "R4") (pin "2") (pinfunction "2_2") (pintype "passive"))
      (node (ref "U2") (pin "4") (pinfunction "VFB_4") (pintype "passive"))
    )
    (net (code "56") (name "Net-(U3-D1)") (class "Default")
      (node (ref "U3") (pin "1") (pinfunction "D1_1") (pintype "passive"))
      (node (ref "U3") (pin "8") (pinfunction "D2_8") (pintype "passive"))
    )
    (net (code "57") (name "Net-(U3-G1)") (class "Default")
      (node (ref "U3") (pin "4") (pinfunction "G1_4") (pintype "passive"))
      (node (ref "U4") (pin "1") (pinfunction "OD_1") (pintype "passive"))
    )
    (net (code "58") (name "Net-(U3-G2)") (class "Default")
      (node (ref "U3") (pin "5") (pinfunction "G2_5") (pintype "passive"))
      (node (ref "U4") (pin "3") (pinfunction "OC_3") (pintype "passive"))
    )
    (net (code "59") (name "Net-(U4-CS)") (class "Default")
      (node (ref "R9") (pin "1") (pinfunction "1_1") (pintype "passive"))
      (node (ref "U4") (pin "2") (pinfunction "CS_2") (pintype "passive"))
    )
    (net (code "60") (name "Net-(U4-VCC)") (class "Default")
      (node (ref "C9") (pin "2") (pinfunction "2_2") (pintype "passive"))
      (node (ref "R10") (pin "1") (pinfunction "1_1") (pintype "passive"))
      (node (ref "U4") (pin "5") (pinfunction "VCC_5") (pintype "passive"))
    )
    (net (code "61") (name "Net-(U5-IO5)") (class "Default")
      (node (ref "R12") (pin "2") (pinfunction "2_2") (pintype "passive"))
      (node (ref "U5") (pin "29") (pinfunction "IO5_29") (pintype "passive"))
    )
    (net (code "62") (name "Net-(U5-IO15)") (class "Default")
      (node (ref "J10") (pin "2") (pinfunction "2_2") (pintype "passive"))
      (node (ref "U5") (pin "23") (pinfunction "IO15_23") (pintype "passive"))
    )
    (net (code "63") (name "Net-(U5-IO18)") (class "Default")
      (node (ref "R13") (pin "2") (pinfunction "2_2") (pintype "passive"))
      (node (ref "U5") (pin "30") (pinfunction "IO18_30") (pintype "passive"))
    )
    (net (code "64") (name "Net-(U5-IO19)") (class "Default")
      (node (ref "R14") (pin "2") (pinfunction "2_2") (pintype "passive"))
      (node (ref "U5") (pin "31") (pinfunction "IO19_31") (pintype "passive"))
    )
    (net (code "65") (name "Net-(U6-EN)") (class "Default")
      (node (ref "C12") (pin "2") (pinfunction "2_2") (pintype "passive"))
      (node (ref "R21") (pin "1") (pinfunction "1_1") (pintype "passive"))
      (node (ref "R22") (pin "2") (pinfunction "2_2") (pintype "passive"))
      (node (ref "U6") (pin "1") (pinfunction "VIN_1") (pintype "passive"))
      (node (ref "U6") (pin "3") (pinfunction "EN_3") (pintype "passive"))
    )
    (net (code "66") (name "VCC") (class "Default")
      (node (ref "C13") (pin "2") (pinfunction "2_2") (pintype "passive"))
      (node (ref "J11") (pin "2") (pinfunction "2_2") (pintype "passive"))
      (node (ref "L1") (pin "1") (pinfunction "1_1") (pintype "passive"))
      (node (ref "R15") (pin "2") (pinfunction "2_2") (pintype "passive"))
      (node (ref "R21") (pin "2") (pinfunction "2_2") (pintype "passive"))
    )
    (net (code "67") (name "unconnected-(U2-X0-Pad13)") (class "Default")
      (node (ref "U2") (pin "13") (pinfunction "X0_13") (pintype "passive"))
    )
    (net (code "68") (name "unconnected-(U4-TD-Pad4)") (class "Default")
      (node (ref "U4") (pin "4") (pinfunction "TD_4") (pintype "passive"))
    )
    (net (code "69") (name "unconnected-(U5-GND-Pad15)") (class "Default")
      (node (ref "U5") (pin "15") (pinfunction "GND_15") (pintype "passive"))
    )
    (net (code "70") (name "unconnected-(U5-NC-Pad32)") (class "Default")
      (node (ref "U5") (pin "32") (pinfunction "NC_32") (pintype "passive"))
    )
    (net (code "71") (name "unconnected-(U6-NC-Pad4)") (class "Default")
      (node (ref "U6") (pin "4") (pinfunction "NC_4") (pintype "passive"))
    )
  )
)
